# G1-4.net
KiCad netlist of a schematic drawn in EAGLE
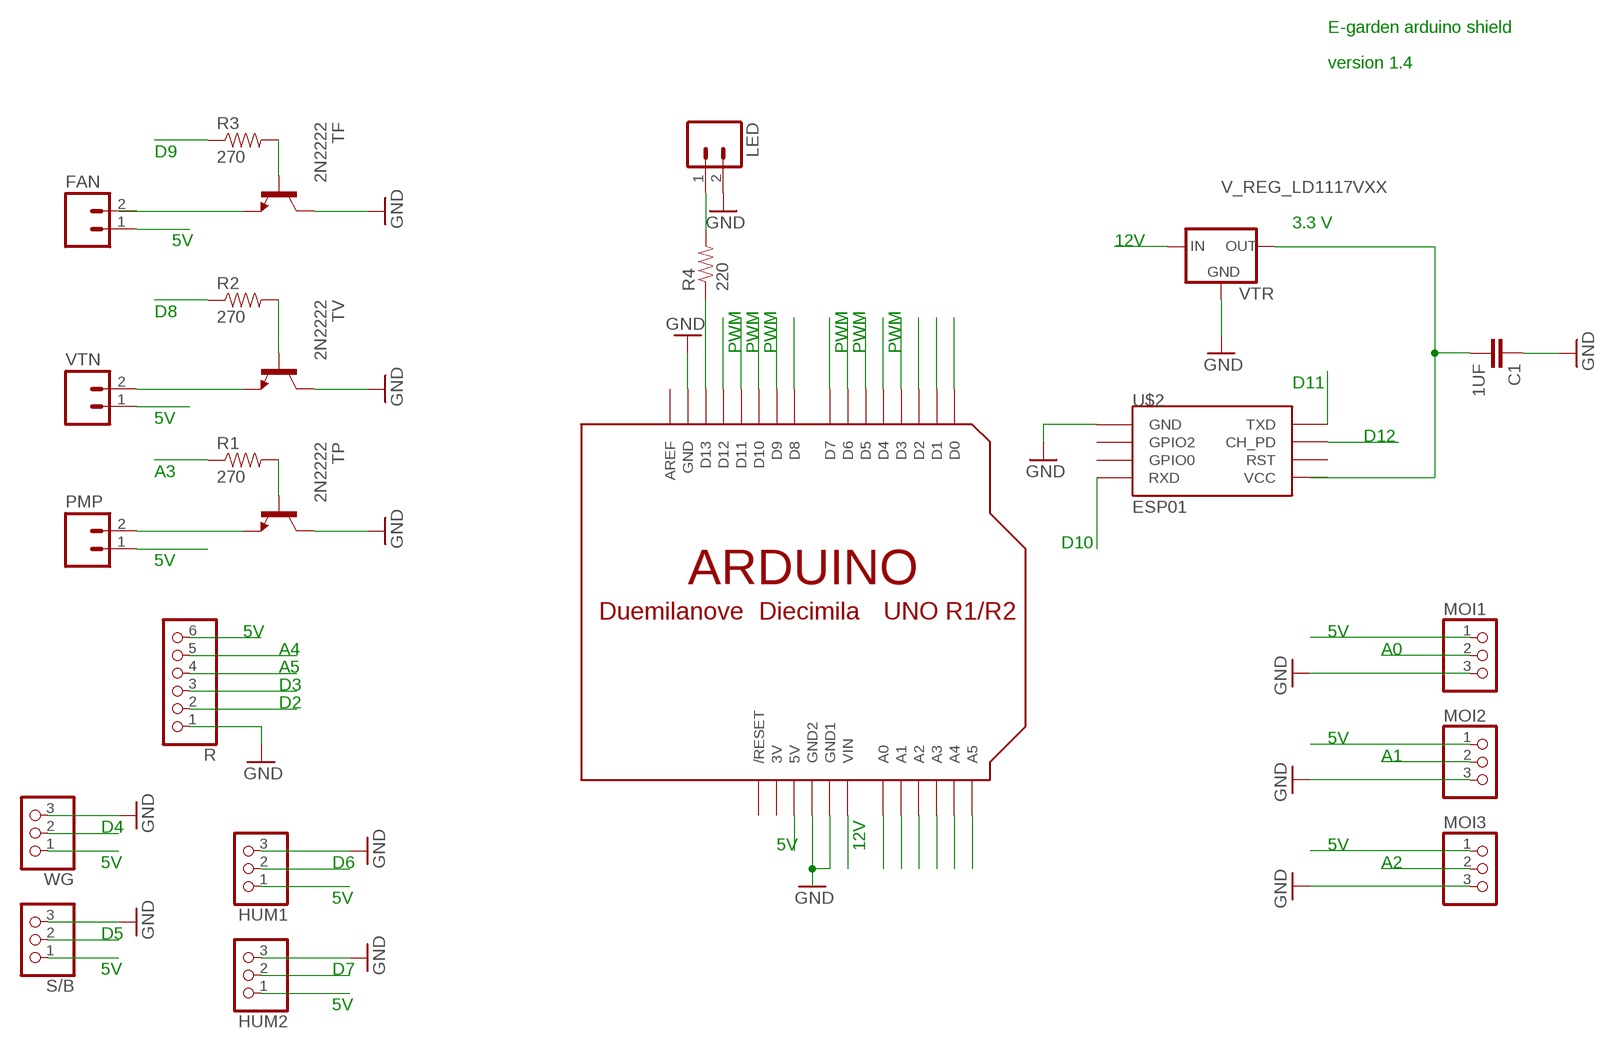
[diagram p0: schematic, sheet 1]

(export (version "E")
  (design (tool "Eeschema 10.0.6"))
  (components
    (comp (ref "C1")
      (value "1UF")
      (footprint "eagle-import:CAP-PTH-SMALL-KIT")
      (libsource (lib "eagle-import") (part "CAPKIT"))
    )
    (comp (ref "FAN")
      (value "M02PTH")
      (footprint "eagle-import:1X02")
      (libsource (lib "eagle-import") (part "M02PTH"))
    )
    (comp (ref "HUM1")
      (value "PINHD-1X3CB")
      (footprint "eagle-import:1X03-CLEANBIG")
      (libsource (lib "eagle-import") (part "PINHD-1X3CB"))
    )
    (comp (ref "HUM2")
      (value "PINHD-1X3CB")
      (footprint "eagle-import:1X03-CLEANBIG")
      (libsource (lib "eagle-import") (part "PINHD-1X3CB"))
    )
    (comp (ref "LED")
      (value "M02PTH")
      (footprint "eagle-import:1X02")
      (libsource (lib "eagle-import") (part "M02PTH"))
    )
    (comp (ref "MOI1")
      (value "PINHD-1X3CB")
      (footprint "eagle-import:1X03-CLEANBIG")
      (libsource (lib "eagle-import") (part "PINHD-1X3CB"))
    )
    (comp (ref "MOI2")
      (value "PINHD-1X3CB")
      (footprint "eagle-import:1X03-CLEANBIG")
      (libsource (lib "eagle-import") (part "PINHD-1X3CB"))
    )
    (comp (ref "MOI3")
      (value "PINHD-1X3CB")
      (footprint "eagle-import:1X03-CLEANBIG")
      (libsource (lib "eagle-import") (part "PINHD-1X3CB"))
    )
    (comp (ref "PMP")
      (value "M02PTH")
      (footprint "eagle-import:1X02")
      (libsource (lib "eagle-import") (part "M02PTH"))
    )
    (comp (ref "R")
      (value "PINHD-1X6CB")
      (footprint "eagle-import:1X06-CLEANBIG")
      (libsource (lib "eagle-import") (part "PINHD-1X6CB"))
    )
    (comp (ref "R1")
      (value "270")
      (footprint "eagle-import:AXIAL-0.4")
      (libsource (lib "eagle-import") (part "RESISTORPTH-1/4W"))
    )
    (comp (ref "R2")
      (value "270")
      (footprint "eagle-import:AXIAL-0.4")
      (libsource (lib "eagle-import") (part "RESISTORPTH-1/4W"))
    )
    (comp (ref "R3")
      (value "270")
      (footprint "eagle-import:AXIAL-0.4")
      (libsource (lib "eagle-import") (part "RESISTORPTH-1/4W"))
    )
    (comp (ref "R4")
      (value "220")
      (footprint "eagle-import:AXIAL-0.4")
      (libsource (lib "eagle-import") (part "RESISTORPTH-1/4W"))
    )
    (comp (ref "S/B")
      (value "PINHD-1X3CB")
      (footprint "eagle-import:1X03-CLEANBIG")
      (libsource (lib "eagle-import") (part "PINHD-1X3CB"))
    )
    (comp (ref "TF")
      (value "2N2222")
      (footprint "eagle-import:TO92-EBC-OVAL")
      (libsource (lib "eagle-import") (part "2N2222"))
    )
    (comp (ref "TP")
      (value "2N2222")
      (footprint "eagle-import:TO92-EBC-OVAL")
      (libsource (lib "eagle-import") (part "2N2222"))
    )
    (comp (ref "TV")
      (value "2N2222")
      (footprint "eagle-import:TO92-EBC-OVAL")
      (libsource (lib "eagle-import") (part "2N2222"))
    )
    (comp (ref "U$1")
      (value "ARDUINO-BPLACE")
      (footprint "eagle-import:ARDUINO-BPLACE")
      (libsource (lib "eagle-import") (part "ARDUINO-BPLACE"))
    )
    (comp (ref "U$2")
      (value "ESP01")
      (footprint "eagle-import:ESP01")
      (libsource (lib "eagle-import") (part "ESP01"))
    )
    (comp (ref "VTN")
      (value "M02PTH")
      (footprint "eagle-import:1X02")
      (libsource (lib "eagle-import") (part "M02PTH"))
    )
    (comp (ref "VTR")
      (value "V_REG_LD1117VXX")
      (footprint "eagle-import:78XXL")
      (libsource (lib "eagle-import") (part "V_REG_LD1117VXX"))
    )
    (comp (ref "WG")
      (value "PINHD-1X3CB")
      (footprint "eagle-import:1X03-CLEANBIG")
      (libsource (lib "eagle-import") (part "PINHD-1X3CB"))
    )
  )
  (nets
    (net (code "1") (name "/3V") (class "Default")
      (node (ref "U$1") (pin "3V") (pinfunction "3V_3V") (pintype "power_in"))
    )
    (net (code "2") (name "/A0") (class "Default")
      (node (ref "MOI1") (pin "2") (pinfunction "2_2") (pintype "passive"))
      (node (ref "U$1") (pin "A0") (pinfunction "A0_A0") (pintype "bidirectional"))
    )
    (net (code "3") (name "/A1") (class "Default")
      (node (ref "MOI2") (pin "2") (pinfunction "2_2") (pintype "passive"))
      (node (ref "U$1") (pin "A1") (pinfunction "A1_A1") (pintype "bidirectional"))
    )
    (net (code "4") (name "/A2") (class "Default")
      (node (ref "MOI3") (pin "2") (pinfunction "2_2") (pintype "passive"))
      (node (ref "U$1") (pin "A2") (pinfunction "A2_A2") (pintype "bidirectional"))
    )
    (net (code "5") (name "/A3") (class "Default")
      (node (ref "R1") (pin "P$1") (pinfunction "1_P$1") (pintype "passive"))
      (node (ref "U$1") (pin "A3") (pinfunction "A3_A3") (pintype "bidirectional"))
    )
    (net (code "6") (name "/A4") (class "Default")
      (node (ref "R") (pin "5") (pinfunction "5_5") (pintype "passive"))
      (node (ref "U$1") (pin "A4") (pinfunction "A4_A4") (pintype "bidirectional"))
    )
    (net (code "7") (name "/A5") (class "Default")
      (node (ref "R") (pin "4") (pinfunction "4_4") (pintype "passive"))
      (node (ref "U$1") (pin "A5") (pinfunction "A5_A5") (pintype "bidirectional"))
    )
    (net (code "8") (name "/D2") (class "Default")
      (node (ref "R") (pin "2") (pinfunction "2_2") (pintype "passive"))
      (node (ref "U$1") (pin "D2") (pinfunction "D2_D2") (pintype "bidirectional"))
    )
    (net (code "9") (name "/D3") (class "Default")
      (node (ref "R") (pin "3") (pinfunction "3_3") (pintype "passive"))
      (node (ref "U$1") (pin "D3") (pinfunction "D3_D3") (pintype "bidirectional"))
    )
    (net (code "10") (name "/D4") (class "Default")
      (node (ref "U$1") (pin "D4") (pinfunction "D4_D4") (pintype "bidirectional"))
      (node (ref "WG") (pin "2") (pinfunction "2_2") (pintype "passive"))
    )
    (net (code "11") (name "/D5") (class "Default")
      (node (ref "S/B") (pin "2") (pinfunction "2_2") (pintype "passive"))
      (node (ref "U$1") (pin "D5") (pinfunction "D5_D5") (pintype "bidirectional"))
    )
    (net (code "12") (name "/D6") (class "Default")
      (node (ref "HUM1") (pin "2") (pinfunction "2_2") (pintype "passive"))
      (node (ref "U$1") (pin "D6") (pinfunction "D6_D6") (pintype "bidirectional"))
    )
    (net (code "13") (name "/D7") (class "Default")
      (node (ref "HUM2") (pin "2") (pinfunction "2_2") (pintype "passive"))
      (node (ref "U$1") (pin "D7") (pinfunction "D7_D7") (pintype "bidirectional"))
    )
    (net (code "14") (name "/D8") (class "Default")
      (node (ref "R2") (pin "P$1") (pinfunction "1_P$1") (pintype "passive"))
      (node (ref "U$1") (pin "D8") (pinfunction "D8_D8") (pintype "bidirectional"))
    )
    (net (code "15") (name "/D9") (class "Default")
      (node (ref "R3") (pin "P$1") (pinfunction "1_P$1") (pintype "passive"))
      (node (ref "U$1") (pin "D9") (pinfunction "D9_D9") (pintype "bidirectional"))
    )
    (net (code "16") (name "/D10") (class "Default")
      (node (ref "U$1") (pin "D10") (pinfunction "D10_D10") (pintype "bidirectional"))
      (node (ref "U$2") (pin "RX") (pinfunction "RXD_RX") (pintype "bidirectional"))
    )
    (net (code "17") (name "/D11") (class "Default")
      (node (ref "U$1") (pin "D11") (pinfunction "D11_D11") (pintype "bidirectional"))
      (node (ref "U$2") (pin "TX") (pinfunction "TXD_TX") (pintype "bidirectional"))
    )
    (net (code "18") (name "/D12") (class "Default")
      (node (ref "U$1") (pin "D12") (pinfunction "D12_D12") (pintype "bidirectional"))
      (node (ref "U$2") (pin "CH_PD") (pinfunction "CH_PD_CH_PD") (pintype "bidirectional"))
    )
    (net (code "19") (name "/V5") (class "Default")
      (node (ref "FAN") (pin "1") (pinfunction "1_1") (pintype "passive"))
      (node (ref "HUM1") (pin "1") (pinfunction "1_1") (pintype "passive"))
      (node (ref "HUM2") (pin "1") (pinfunction "1_1") (pintype "passive"))
      (node (ref "MOI1") (pin "1") (pinfunction "1_1") (pintype "passive"))
      (node (ref "MOI2") (pin "1") (pinfunction "1_1") (pintype "passive"))
      (node (ref "MOI3") (pin "1") (pinfunction "1_1") (pintype "passive"))
      (node (ref "PMP") (pin "1") (pinfunction "1_1") (pintype "passive"))
      (node (ref "R") (pin "6") (pinfunction "6_6") (pintype "passive"))
      (node (ref "S/B") (pin "1") (pinfunction "1_1") (pintype "passive"))
      (node (ref "U$1") (pin "5V") (pinfunction "5V_5V") (pintype "power_in"))
      (node (ref "VTN") (pin "1") (pinfunction "1_1") (pintype "passive"))
      (node (ref "WG") (pin "1") (pinfunction "1_1") (pintype "passive"))
    )
    (net (code "20") (name "/V12") (class "Default")
      (node (ref "U$1") (pin "VIN") (pinfunction "VIN_VIN") (pintype "power_in"))
      (node (ref "VTR") (pin "OUT") (pinfunction "IN_OUT") (pintype "input"))
    )
    (net (code "21") (name "GND") (class "Default")
      (node (ref "C1") (pin "1") (pinfunction "1_1") (pintype "passive"))
      (node (ref "HUM1") (pin "3") (pinfunction "3_3") (pintype "passive"))
      (node (ref "HUM2") (pin "3") (pinfunction "3_3") (pintype "passive"))
      (node (ref "LED") (pin "2") (pinfunction "2_2") (pintype "passive"))
      (node (ref "MOI1") (pin "3") (pinfunction "3_3") (pintype "passive"))
      (node (ref "MOI2") (pin "3") (pinfunction "3_3") (pintype "passive"))
      (node (ref "MOI3") (pin "3") (pinfunction "3_3") (pintype "passive"))
      (node (ref "R") (pin "1") (pinfunction "1_1") (pintype "passive"))
      (node (ref "S/B") (pin "3") (pinfunction "3_3") (pintype "passive"))
      (node (ref "TF") (pin "C") (pinfunction "C_C") (pintype "passive"))
      (node (ref "TP") (pin "C") (pinfunction "C_C") (pintype "passive"))
      (node (ref "TV") (pin "C") (pinfunction "C_C") (pintype "passive"))
      (node (ref "U$1") (pin "GND") (pinfunction "GND_GND") (pintype "power_in"))
      (node (ref "U$1") (pin "GND1") (pinfunction "GND1_GND1") (pintype "power_in"))
      (node (ref "U$1") (pin "GND2") (pinfunction "GND2_GND2") (pintype "power_in"))
      (node (ref "U$2") (pin "GND") (pinfunction "GND_GND") (pintype "bidirectional"))
      (node (ref "VTR") (pin "IN") (pinfunction "GND_IN") (pintype "input"))
      (node (ref "WG") (pin "3") (pinfunction "3_3") (pintype "passive"))
    )
    (net (code "22") (name "Net-(FAN-Pad2)") (class "Default")
      (node (ref "FAN") (pin "2") (pinfunction "2_2") (pintype "passive"))
      (node (ref "TF") (pin "E") (pinfunction "E_E") (pintype "passive"))
    )
    (net (code "23") (name "Net-(PMP-Pad2)") (class "Default")
      (node (ref "PMP") (pin "2") (pinfunction "2_2") (pintype "passive"))
      (node (ref "TP") (pin "E") (pinfunction "E_E") (pintype "passive"))
    )
    (net (code "24") (name "Net-(R1-2)") (class "Default")
      (node (ref "R1") (pin "P$2") (pinfunction "2_P$2") (pintype "passive"))
      (node (ref "TP") (pin "B") (pinfunction "B_B") (pintype "passive"))
    )
    (net (code "25") (name "Net-(R2-2)") (class "Default")
      (node (ref "R2") (pin "P$2") (pinfunction "2_P$2") (pintype "passive"))
      (node (ref "TV") (pin "B") (pinfunction "B_B") (pintype "passive"))
    )
    (net (code "26") (name "Net-(R3-2)") (class "Default")
      (node (ref "R3") (pin "P$2") (pinfunction "2_P$2") (pintype "passive"))
      (node (ref "TF") (pin "B") (pinfunction "B_B") (pintype "passive"))
    )
    (net (code "27") (name "Net-(R4-1)") (class "Default")
      (node (ref "R4") (pin "P$1") (pinfunction "1_P$1") (pintype "passive"))
      (node (ref "U$1") (pin "D13") (pinfunction "D13_D13") (pintype "bidirectional"))
    )
    (net (code "28") (name "Net-(R4-2)") (class "Default")
      (node (ref "LED") (pin "1") (pinfunction "1_1") (pintype "passive"))
      (node (ref "R4") (pin "P$2") (pinfunction "2_P$2") (pintype "passive"))
    )
    (net (code "29") (name "Net-(TV-PadE)") (class "Default")
      (node (ref "TV") (pin "E") (pinfunction "E_E") (pintype "passive"))
      (node (ref "VTN") (pin "2") (pinfunction "2_2") (pintype "passive"))
    )
    (net (code "30") (name "Net-(VTR-OUT)") (class "Default")
      (node (ref "C1") (pin "2") (pinfunction "2_2") (pintype "passive"))
      (node (ref "U$2") (pin "VCC") (pinfunction "VCC_VCC") (pintype "bidirectional"))
      (node (ref "VTR") (pin "GND") (pinfunction "OUT_GND") (pintype "passive"))
    )
    (net (code "31") (name "unconnected-(U$1-PadAREF)") (class "Default")
      (node (ref "U$1") (pin "AREF") (pinfunction "AREF_AREF") (pintype "bidirectional"))
    )
    (net (code "32") (name "unconnected-(U$1-PadD0)") (class "Default")
      (node (ref "U$1") (pin "D0") (pinfunction "D0_D0") (pintype "bidirectional"))
    )
    (net (code "33") (name "unconnected-(U$1-PadD1)") (class "Default")
      (node (ref "U$1") (pin "D1") (pinfunction "D1_D1") (pintype "bidirectional"))
    )
    (net (code "34") (name "unconnected-(U$1-{slash}RESET-PadRESET)") (class "Default")
      (node (ref "U$1") (pin "RESET") (pinfunction "/RESET_RESET") (pintype "bidirectional"))
    )
    (net (code "35") (name "unconnected-(U$2-PadGPIO0)") (class "Default")
      (node (ref "U$2") (pin "GPIO0") (pinfunction "GPIO0_GPIO0") (pintype "bidirectional"))
    )
    (net (code "36") (name "unconnected-(U$2-PadGPIO2)") (class "Default")
      (node (ref "U$2") (pin "GPIO2") (pinfunction "GPIO2_GPIO2") (pintype "bidirectional"))
    )
    (net (code "37") (name "unconnected-(U$2-PadRST)") (class "Default")
      (node (ref "U$2") (pin "RST") (pinfunction "RST_RST") (pintype "bidirectional"))
    )
  )
)
